# design.net
KiCad netlist of a schematic drawn in Altium Designer
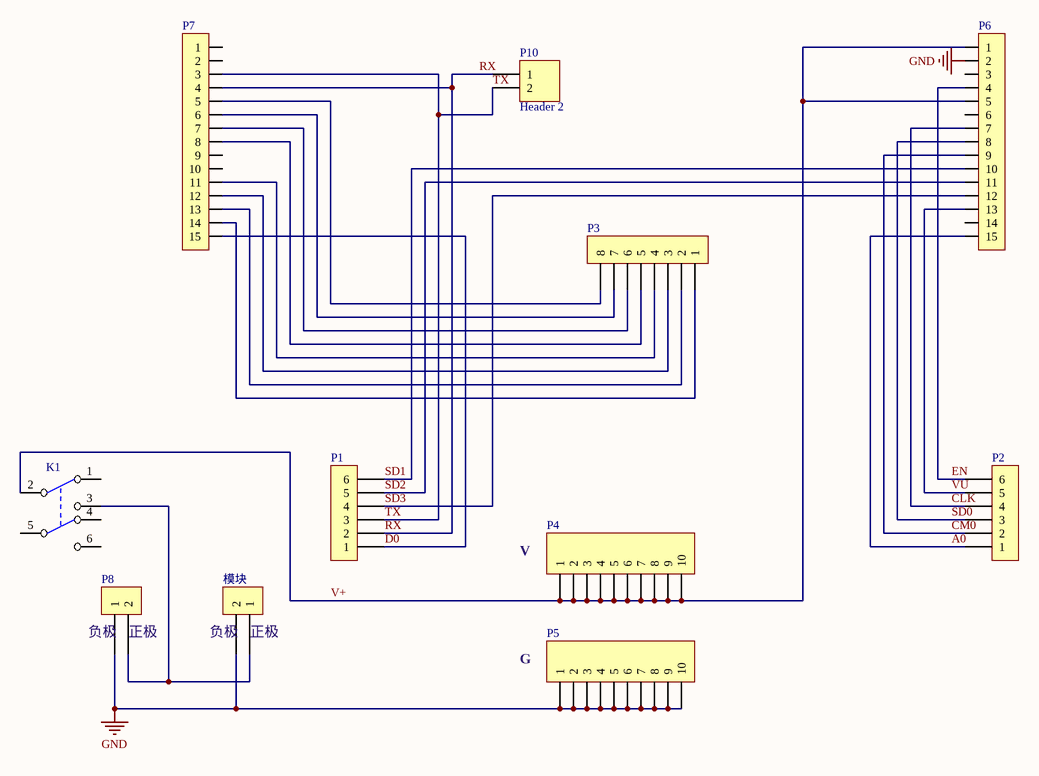
[diagram p0: 原理图.SchDoc]

(export (version "E")
  (design (tool "Eeschema 10.0.6"))
  (components
    (comp (ref "K1")
      (value "~")
      (footprint "K-7*7mm")
      (description "双刀双执开关")
      (libsource (lib "其它器件") (part "SW-DPDT"))
    )
    (comp (ref "P1") (value "~") (footprint "SIP6") (libsource (lib "") (part "6P_1")))
    (comp (ref "P2") (value "~") (footprint "SIP6") (libsource (lib "接插件") (part "6P")))
    (comp (ref "P3") (value "~") (footprint "SIP8") (libsource (lib "接插件") (part "8P")))
    (comp (ref "P4") (value "~") (footprint "SIP10") (libsource (lib "接插件") (part "10P")))
    (comp (ref "P5") (value "~") (footprint "SIP10") (libsource (lib "接插件") (part "10P")))
    (comp (ref "P6") (value "~") (footprint "SIP15") (libsource (lib "") (part "15P_1")))
    (comp (ref "P7") (value "~") (footprint "SIP15") (libsource (lib "接插件") (part "15P")))
    (comp (ref "P8") (value "~") (footprint "DIP2") (libsource (lib "烤杯机电源") (part "CON1")))
    (comp (ref "P9") (value "模块") (footprint "SIP2") (libsource (lib "") (part "CON1_1")))
    (comp (ref "P10")
      (value "Header 2")
      (footprint "HDR1X2")
      (description "Header, 2-Pin")
      (fields (field (name "PUBLISHER") "Altium Limited"))
      (libsource (lib "Miscellaneous Connectors") (part "Header 2"))
    )
  )
  (nets
    (net (code "1") (name "/A0") (class "Default")
      (node (ref "P2") (pin "1") (pinfunction "1_1") (pintype "passive"))
      (node (ref "P6") (pin "15") (pinfunction "15_15") (pintype "passive"))
    )
    (net (code "2") (name "/CLK") (class "Default")
      (node (ref "P2") (pin "4") (pinfunction "4_4") (pintype "passive"))
      (node (ref "P6") (pin "7") (pinfunction "7_7") (pintype "passive"))
    )
    (net (code "3") (name "/CM0") (class "Default")
      (node (ref "P2") (pin "2") (pinfunction "2_2") (pintype "passive"))
      (node (ref "P6") (pin "9") (pinfunction "9_9") (pintype "passive"))
    )
    (net (code "4") (name "/D0") (class "Default")
      (node (ref "P1") (pin "1") (pinfunction "1_1") (pintype "passive"))
      (node (ref "P7") (pin "15") (pinfunction "15_15") (pintype "passive"))
    )
    (net (code "5") (name "/EN") (class "Default")
      (node (ref "P2") (pin "6") (pinfunction "6_6") (pintype "passive"))
      (node (ref "P6") (pin "4") (pinfunction "4_4") (pintype "passive"))
    )
    (net (code "6") (name "/RX") (class "Default")
      (node (ref "P1") (pin "2") (pinfunction "2_2") (pintype "passive"))
      (node (ref "P10") (pin "1") (pinfunction "1_1") (pintype "passive"))
      (node (ref "P7") (pin "4") (pinfunction "4_4") (pintype "passive"))
    )
    (net (code "7") (name "/SD0") (class "Default")
      (node (ref "P2") (pin "3") (pinfunction "3_3") (pintype "passive"))
      (node (ref "P6") (pin "8") (pinfunction "8_8") (pintype "passive"))
    )
    (net (code "8") (name "/SD1") (class "Default")
      (node (ref "P1") (pin "6") (pinfunction "6_6") (pintype "passive"))
      (node (ref "P6") (pin "10") (pinfunction "10_10") (pintype "passive"))
    )
    (net (code "9") (name "/SD2") (class "Default")
      (node (ref "P1") (pin "5") (pinfunction "5_5") (pintype "passive"))
      (node (ref "P6") (pin "11") (pinfunction "11_11") (pintype "passive"))
    )
    (net (code "10") (name "/SD3") (class "Default")
      (node (ref "P1") (pin "4") (pinfunction "4_4") (pintype "passive"))
      (node (ref "P6") (pin "12") (pinfunction "12_12") (pintype "passive"))
    )
    (net (code "11") (name "/TX") (class "Default")
      (node (ref "P1") (pin "3") (pinfunction "3_3") (pintype "passive"))
      (node (ref "P10") (pin "2") (pinfunction "2_2") (pintype "passive"))
      (node (ref "P7") (pin "3") (pinfunction "3_3") (pintype "passive"))
    )
    (net (code "12") (name "/V+") (class "Default")
      (node (ref "K1") (pin "2") (pinfunction "2_2") (pintype "passive"))
      (node (ref "P4") (pin "1") (pinfunction "1_1") (pintype "passive"))
      (node (ref "P4") (pin "10") (pinfunction "10_10") (pintype "passive"))
      (node (ref "P4") (pin "2") (pinfunction "2_2") (pintype "passive"))
      (node (ref "P4") (pin "3") (pinfunction "3_3") (pintype "passive"))
      (node (ref "P4") (pin "4") (pinfunction "4_4") (pintype "passive"))
      (node (ref "P4") (pin "5") (pinfunction "5_5") (pintype "passive"))
      (node (ref "P4") (pin "6") (pinfunction "6_6") (pintype "passive"))
      (node (ref "P4") (pin "7") (pinfunction "7_7") (pintype "passive"))
      (node (ref "P4") (pin "8") (pinfunction "8_8") (pintype "passive"))
      (node (ref "P4") (pin "9") (pinfunction "9_9") (pintype "passive"))
      (node (ref "P6") (pin "1") (pinfunction "1_1") (pintype "passive"))
      (node (ref "P6") (pin "5") (pinfunction "5_5") (pintype "passive"))
    )
    (net (code "13") (name "/VU") (class "Default")
      (node (ref "P2") (pin "5") (pinfunction "5_5") (pintype "passive"))
      (node (ref "P6") (pin "13") (pinfunction "13_13") (pintype "passive"))
    )
    (net (code "14") (name "GND") (class "Default")
      (node (ref "P5") (pin "1") (pinfunction "1_1") (pintype "passive"))
      (node (ref "P5") (pin "10") (pinfunction "10_10") (pintype "passive"))
      (node (ref "P5") (pin "2") (pinfunction "2_2") (pintype "passive"))
      (node (ref "P5") (pin "3") (pinfunction "3_3") (pintype "passive"))
      (node (ref "P5") (pin "4") (pinfunction "4_4") (pintype "passive"))
      (node (ref "P5") (pin "5") (pinfunction "5_5") (pintype "passive"))
      (node (ref "P5") (pin "6") (pinfunction "6_6") (pintype "passive"))
      (node (ref "P5") (pin "7") (pinfunction "7_7") (pintype "passive"))
      (node (ref "P5") (pin "8") (pinfunction "8_8") (pintype "passive"))
      (node (ref "P5") (pin "9") (pinfunction "9_9") (pintype "passive"))
      (node (ref "P6") (pin "2") (pinfunction "2_2") (pintype "passive"))
      (node (ref "P8") (pin "1") (pinfunction "1_1") (pintype "passive"))
      (node (ref "P9") (pin "2") (pinfunction "2_2") (pintype "passive"))
    )
    (net (code "15") (name "Net-(K1-Pad3)") (class "Default")
      (node (ref "K1") (pin "3") (pinfunction "3_3") (pintype "passive"))
      (node (ref "P8") (pin "2") (pinfunction "2_2") (pintype "passive"))
      (node (ref "P9") (pin "1") (pinfunction "1_1") (pintype "passive"))
    )
    (net (code "16") (name "Net-(P3-Pad1)") (class "Default")
      (node (ref "P3") (pin "1") (pinfunction "1_1") (pintype "passive"))
      (node (ref "P7") (pin "14") (pinfunction "14_14") (pintype "passive"))
    )
    (net (code "17") (name "Net-(P3-Pad2)") (class "Default")
      (node (ref "P3") (pin "2") (pinfunction "2_2") (pintype "passive"))
      (node (ref "P7") (pin "13") (pinfunction "13_13") (pintype "passive"))
    )
    (net (code "18") (name "Net-(P3-Pad3)") (class "Default")
      (node (ref "P3") (pin "3") (pinfunction "3_3") (pintype "passive"))
      (node (ref "P7") (pin "12") (pinfunction "12_12") (pintype "passive"))
    )
    (net (code "19") (name "Net-(P3-Pad4)") (class "Default")
      (node (ref "P3") (pin "4") (pinfunction "4_4") (pintype "passive"))
      (node (ref "P7") (pin "11") (pinfunction "11_11") (pintype "passive"))
    )
    (net (code "20") (name "Net-(P3-Pad5)") (class "Default")
      (node (ref "P3") (pin "5") (pinfunction "5_5") (pintype "passive"))
      (node (ref "P7") (pin "8") (pinfunction "8_8") (pintype "passive"))
    )
    (net (code "21") (name "Net-(P3-Pad6)") (class "Default")
      (node (ref "P3") (pin "6") (pinfunction "6_6") (pintype "passive"))
      (node (ref "P7") (pin "7") (pinfunction "7_7") (pintype "passive"))
    )
    (net (code "22") (name "Net-(P3-Pad7)") (class "Default")
      (node (ref "P3") (pin "7") (pinfunction "7_7") (pintype "passive"))
      (node (ref "P7") (pin "6") (pinfunction "6_6") (pintype "passive"))
    )
    (net (code "23") (name "Net-(P3-Pad8)") (class "Default")
      (node (ref "P3") (pin "8") (pinfunction "8_8") (pintype "passive"))
      (node (ref "P7") (pin "5") (pinfunction "5_5") (pintype "passive"))
    )
    (net (code "24") (name "unconnected-(K1-Pad1)") (class "Default")
      (node (ref "K1") (pin "1") (pinfunction "1_1") (pintype "passive"))
    )
    (net (code "25") (name "unconnected-(K1-Pad4)") (class "Default")
      (node (ref "K1") (pin "4") (pinfunction "4_4") (pintype "passive"))
    )
    (net (code "26") (name "unconnected-(K1-Pad5)") (class "Default")
      (node (ref "K1") (pin "5") (pinfunction "5_5") (pintype "passive"))
    )
    (net (code "27") (name "unconnected-(K1-Pad6)") (class "Default")
      (node (ref "K1") (pin "6") (pinfunction "6_6") (pintype "passive"))
    )
    (net (code "28") (name "unconnected-(P6-Pad3)") (class "Default")
      (node (ref "P6") (pin "3") (pinfunction "3_3") (pintype "passive"))
    )
    (net (code "29") (name "unconnected-(P6-Pad6)") (class "Default")
      (node (ref "P6") (pin "6") (pinfunction "6_6") (pintype "passive"))
    )
    (net (code "30") (name "unconnected-(P6-Pad14)") (class "Default")
      (node (ref "P6") (pin "14") (pinfunction "14_14") (pintype "passive"))
    )
    (net (code "31") (name "unconnected-(P7-Pad1)") (class "Default")
      (node (ref "P7") (pin "1") (pinfunction "1_1") (pintype "passive"))
    )
    (net (code "32") (name "unconnected-(P7-Pad2)") (class "Default")
      (node (ref "P7") (pin "2") (pinfunction "2_2") (pintype "passive"))
    )
    (net (code "33") (name "unconnected-(P7-Pad9)") (class "Default")
      (node (ref "P7") (pin "9") (pinfunction "9_9") (pintype "passive"))
    )
    (net (code "34") (name "unconnected-(P7-Pad10)") (class "Default")
      (node (ref "P7") (pin "10") (pinfunction "10_10") (pintype "passive"))
    )
  )
)
